# T4p0.net
KiCad netlist of a schematic drawn in EAGLE
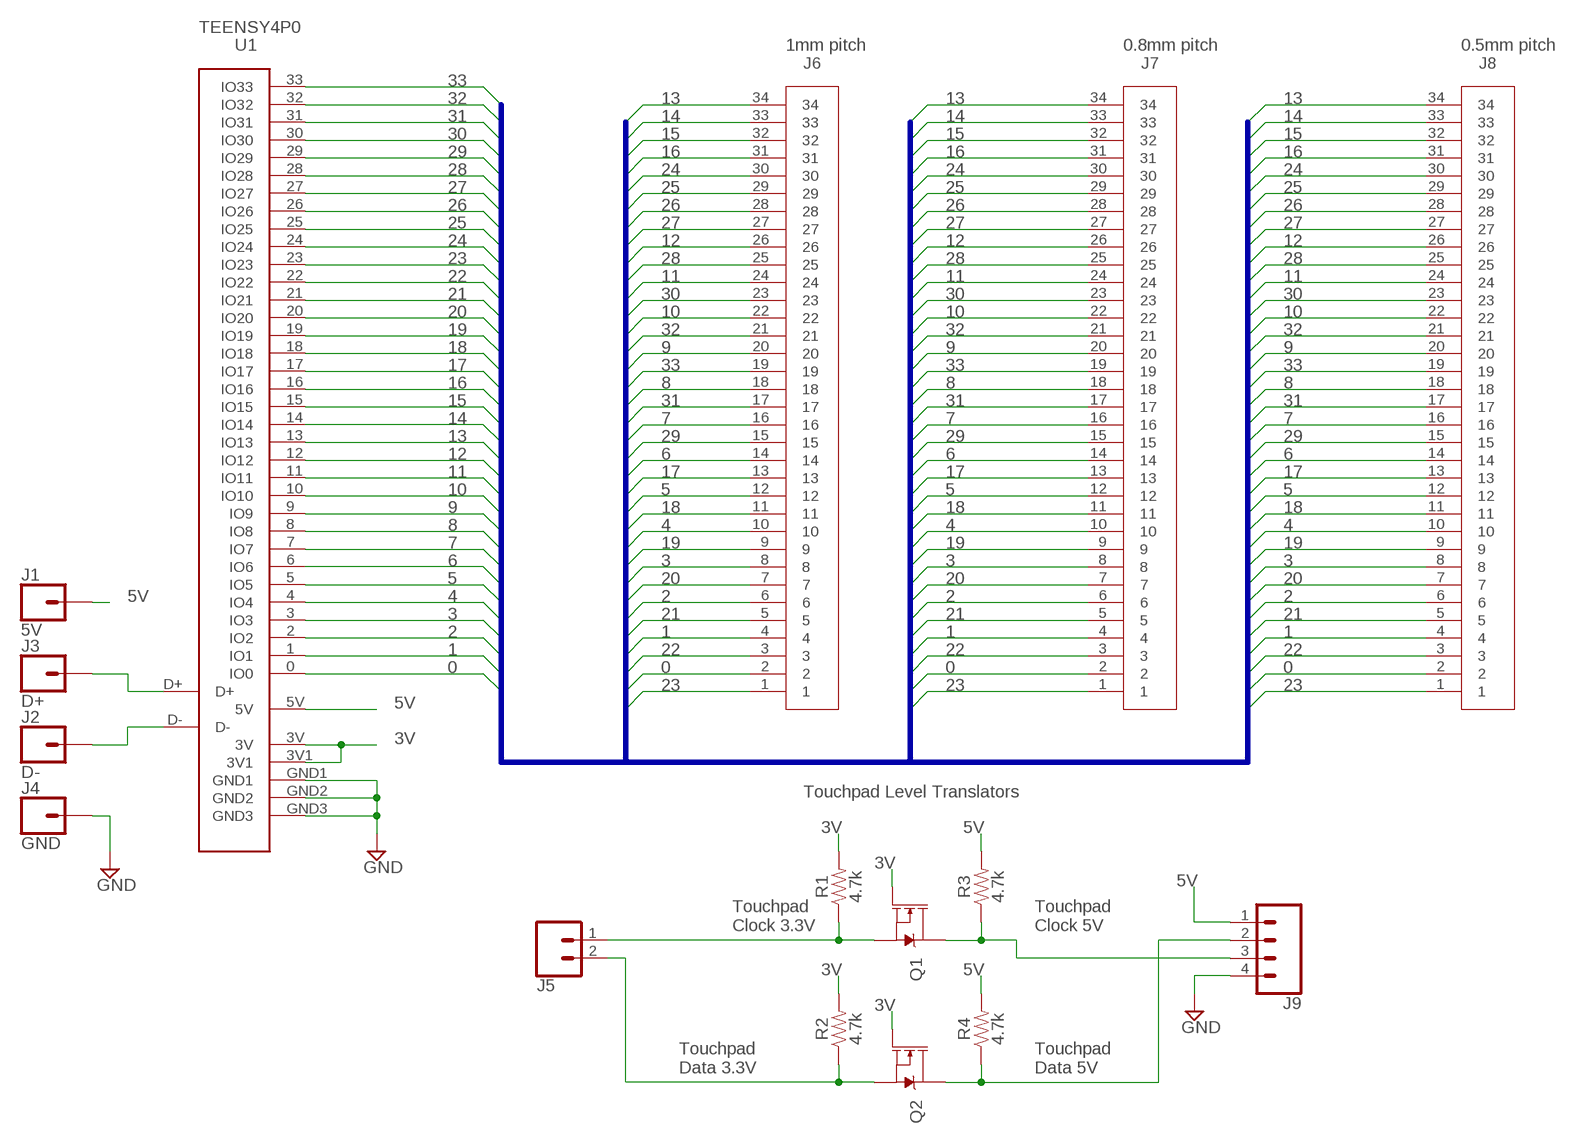
[diagram p0: schematic, sheet 1]

(export (version "E")
  (design (tool "Eeschema 10.0.6"))
  (components
    (comp (ref "J1")
      (value "5V")
      (footprint "eagle-import:1X01_NO_SILK")
      (libsource (lib "eagle-import") (part "CONN_01PTH_NO_SILK_YES_STOP"))
    )
    (comp (ref "J2")
      (value "D-")
      (footprint "eagle-import:1X01_NO_SILK")
      (libsource (lib "eagle-import") (part "CONN_01PTH_NO_SILK_YES_STOP"))
    )
    (comp (ref "J3")
      (value "D+")
      (footprint "eagle-import:1X01_NO_SILK")
      (libsource (lib "eagle-import") (part "CONN_01PTH_NO_SILK_YES_STOP"))
    )
    (comp (ref "J4")
      (value "GND")
      (footprint "eagle-import:1X01_NO_SILK")
      (libsource (lib "eagle-import") (part "CONN_01PTH_NO_SILK_YES_STOP"))
    )
    (comp (ref "J5")
      (value "CONN_021X02_NO_SILK")
      (footprint "eagle-import:1X02_NO_SILK")
      (libsource (lib "eagle-import") (part "CONN_021X02_NO_SILK"))
    )
    (comp (ref "J6")
      (value "FPC34")
      (footprint "eagle-import:FPC34")
      (libsource (lib "eagle-import") (part "FPC34"))
    )
    (comp (ref "J7")
      (value "FPC34_P8MM")
      (footprint "eagle-import:FPC34_P8MM")
      (libsource (lib "eagle-import") (part "FPC34_P8MM"))
    )
    (comp (ref "J8")
      (value "FPC34_P5MM")
      (footprint "eagle-import:FPC34_P5MM")
      (libsource (lib "eagle-import") (part "FPC34_P5MM"))
    )
    (comp (ref "J9")
      (value "CONN_041X04_NO_SILK")
      (footprint "eagle-import:1X04_NO_SILK")
      (libsource (lib "eagle-import") (part "CONN_041X04_NO_SILK"))
    )
    (comp (ref "Q1")
      (value "220mA/50V/3.5Ω")
      (footprint "eagle-import:SOT23-3")
      (libsource (lib "eagle-import") (part "MOSFET-NCH-BSS138"))
    )
    (comp (ref "Q2")
      (value "220mA/50V/3.5Ω")
      (footprint "eagle-import:SOT23-3")
      (libsource (lib "eagle-import") (part "MOSFET-NCH-BSS138"))
    )
    (comp (ref "R1")
      (value "4.7k")
      (footprint "eagle-import:0603")
      (libsource (lib "eagle-import") (part "4.7KOHM-0603-1/10W-1%"))
    )
    (comp (ref "R2")
      (value "4.7k")
      (footprint "eagle-import:0603")
      (libsource (lib "eagle-import") (part "4.7KOHM-0603-1/10W-1%"))
    )
    (comp (ref "R3")
      (value "4.7k")
      (footprint "eagle-import:0603")
      (libsource (lib "eagle-import") (part "4.7KOHM-0603-1/10W-1%"))
    )
    (comp (ref "R4")
      (value "4.7k")
      (footprint "eagle-import:0603")
      (libsource (lib "eagle-import") (part "4.7KOHM-0603-1/10W-1%"))
    )
    (comp (ref "U1")
      (value "TEENSY4P0")
      (footprint "eagle-import:TEENSY4P0")
      (libsource (lib "eagle-import") (part "TEENSY4P0"))
    )
  )
  (nets
    (net (code "1") (name "/0") (class "Default")
      (node (ref "J6") (pin "2") (pinfunction "2_2") (pintype "bidirectional"))
      (node (ref "J7") (pin "2") (pinfunction "2_2") (pintype "bidirectional"))
      (node (ref "J8") (pin "2") (pinfunction "2_2") (pintype "bidirectional"))
      (node (ref "U1") (pin "0") (pinfunction "IO0_0") (pintype "bidirectional"))
    )
    (net (code "2") (name "/1") (class "Default")
      (node (ref "J6") (pin "4") (pinfunction "4_4") (pintype "bidirectional"))
      (node (ref "J7") (pin "4") (pinfunction "4_4") (pintype "bidirectional"))
      (node (ref "J8") (pin "4") (pinfunction "4_4") (pintype "bidirectional"))
      (node (ref "U1") (pin "1") (pinfunction "IO1_1") (pintype "bidirectional"))
    )
    (net (code "3") (name "/2") (class "Default")
      (node (ref "J6") (pin "6") (pinfunction "6_6") (pintype "bidirectional"))
      (node (ref "J7") (pin "6") (pinfunction "6_6") (pintype "bidirectional"))
      (node (ref "J8") (pin "6") (pinfunction "6_6") (pintype "bidirectional"))
      (node (ref "U1") (pin "2") (pinfunction "IO2_2") (pintype "bidirectional"))
    )
    (net (code "4") (name "/3") (class "Default")
      (node (ref "J6") (pin "8") (pinfunction "8_8") (pintype "bidirectional"))
      (node (ref "J7") (pin "8") (pinfunction "8_8") (pintype "bidirectional"))
      (node (ref "J8") (pin "8") (pinfunction "8_8") (pintype "bidirectional"))
      (node (ref "U1") (pin "3") (pinfunction "IO3_3") (pintype "bidirectional"))
    )
    (net (code "5") (name "/3V") (class "Default")
      (node (ref "Q1") (pin "1") (pinfunction "G_1") (pintype "bidirectional"))
      (node (ref "Q2") (pin "1") (pinfunction "G_1") (pintype "bidirectional"))
      (node (ref "R1") (pin "2") (pinfunction "2_2") (pintype "passive"))
      (node (ref "R2") (pin "2") (pinfunction "2_2") (pintype "passive"))
      (node (ref "U1") (pin "3V") (pinfunction "3V_3V") (pintype "bidirectional"))
      (node (ref "U1") (pin "3V1") (pinfunction "3V1_3V1") (pintype "bidirectional"))
    )
    (net (code "6") (name "/4") (class "Default")
      (node (ref "J6") (pin "10") (pinfunction "10_10") (pintype "bidirectional"))
      (node (ref "J7") (pin "10") (pinfunction "10_10") (pintype "bidirectional"))
      (node (ref "J8") (pin "10") (pinfunction "10_10") (pintype "bidirectional"))
      (node (ref "U1") (pin "4") (pinfunction "IO4_4") (pintype "bidirectional"))
    )
    (net (code "7") (name "/5") (class "Default")
      (node (ref "J6") (pin "12") (pinfunction "12_12") (pintype "bidirectional"))
      (node (ref "J7") (pin "12") (pinfunction "12_12") (pintype "bidirectional"))
      (node (ref "J8") (pin "12") (pinfunction "12_12") (pintype "bidirectional"))
      (node (ref "U1") (pin "5") (pinfunction "IO5_5") (pintype "bidirectional"))
    )
    (net (code "8") (name "/5V") (class "Default")
      (node (ref "J1") (pin "1") (pinfunction "1_1") (pintype "passive"))
      (node (ref "J9") (pin "1") (pinfunction "1_1") (pintype "passive"))
      (node (ref "R3") (pin "2") (pinfunction "2_2") (pintype "passive"))
      (node (ref "R4") (pin "2") (pinfunction "2_2") (pintype "passive"))
      (node (ref "U1") (pin "5V") (pinfunction "5V_5V") (pintype "bidirectional"))
    )
    (net (code "9") (name "/6") (class "Default")
      (node (ref "J6") (pin "14") (pinfunction "14_14") (pintype "bidirectional"))
      (node (ref "J7") (pin "14") (pinfunction "14_14") (pintype "bidirectional"))
      (node (ref "J8") (pin "14") (pinfunction "14_14") (pintype "bidirectional"))
      (node (ref "U1") (pin "6") (pinfunction "IO6_6") (pintype "bidirectional"))
    )
    (net (code "10") (name "/7") (class "Default")
      (node (ref "J6") (pin "16") (pinfunction "16_16") (pintype "bidirectional"))
      (node (ref "J7") (pin "16") (pinfunction "16_16") (pintype "bidirectional"))
      (node (ref "J8") (pin "16") (pinfunction "16_16") (pintype "bidirectional"))
      (node (ref "U1") (pin "7") (pinfunction "IO7_7") (pintype "bidirectional"))
    )
    (net (code "11") (name "/8") (class "Default")
      (node (ref "J6") (pin "18") (pinfunction "18_18") (pintype "bidirectional"))
      (node (ref "J7") (pin "18") (pinfunction "18_18") (pintype "bidirectional"))
      (node (ref "J8") (pin "18") (pinfunction "18_18") (pintype "bidirectional"))
      (node (ref "U1") (pin "8") (pinfunction "IO8_8") (pintype "bidirectional"))
    )
    (net (code "12") (name "/9") (class "Default")
      (node (ref "J6") (pin "20") (pinfunction "20_20") (pintype "bidirectional"))
      (node (ref "J7") (pin "20") (pinfunction "20_20") (pintype "bidirectional"))
      (node (ref "J8") (pin "20") (pinfunction "20_20") (pintype "bidirectional"))
      (node (ref "U1") (pin "9") (pinfunction "IO9_9") (pintype "bidirectional"))
    )
    (net (code "13") (name "/10") (class "Default")
      (node (ref "J6") (pin "22") (pinfunction "22_22") (pintype "bidirectional"))
      (node (ref "J7") (pin "22") (pinfunction "22_22") (pintype "bidirectional"))
      (node (ref "J8") (pin "22") (pinfunction "22_22") (pintype "bidirectional"))
      (node (ref "U1") (pin "10") (pinfunction "IO10_10") (pintype "bidirectional"))
    )
    (net (code "14") (name "/11") (class "Default")
      (node (ref "J6") (pin "24") (pinfunction "24_24") (pintype "bidirectional"))
      (node (ref "J7") (pin "24") (pinfunction "24_24") (pintype "bidirectional"))
      (node (ref "J8") (pin "24") (pinfunction "24_24") (pintype "bidirectional"))
      (node (ref "U1") (pin "11") (pinfunction "IO11_11") (pintype "bidirectional"))
    )
    (net (code "15") (name "/12") (class "Default")
      (node (ref "J6") (pin "26") (pinfunction "26_26") (pintype "bidirectional"))
      (node (ref "J7") (pin "26") (pinfunction "26_26") (pintype "bidirectional"))
      (node (ref "J8") (pin "26") (pinfunction "26_26") (pintype "bidirectional"))
      (node (ref "U1") (pin "12") (pinfunction "IO12_12") (pintype "bidirectional"))
    )
    (net (code "16") (name "/13") (class "Default")
      (node (ref "J6") (pin "34") (pinfunction "34_34") (pintype "bidirectional"))
      (node (ref "J7") (pin "34") (pinfunction "34_34") (pintype "bidirectional"))
      (node (ref "J8") (pin "34") (pinfunction "34_34") (pintype "bidirectional"))
      (node (ref "U1") (pin "13") (pinfunction "IO13_13") (pintype "bidirectional"))
    )
    (net (code "17") (name "/14") (class "Default")
      (node (ref "J6") (pin "33") (pinfunction "33_33") (pintype "bidirectional"))
      (node (ref "J7") (pin "33") (pinfunction "33_33") (pintype "bidirectional"))
      (node (ref "J8") (pin "33") (pinfunction "33_33") (pintype "bidirectional"))
      (node (ref "U1") (pin "14") (pinfunction "IO14_14") (pintype "bidirectional"))
    )
    (net (code "18") (name "/15") (class "Default")
      (node (ref "J6") (pin "32") (pinfunction "32_32") (pintype "bidirectional"))
      (node (ref "J7") (pin "32") (pinfunction "32_32") (pintype "bidirectional"))
      (node (ref "J8") (pin "32") (pinfunction "32_32") (pintype "bidirectional"))
      (node (ref "U1") (pin "15") (pinfunction "IO15_15") (pintype "bidirectional"))
    )
    (net (code "19") (name "/16") (class "Default")
      (node (ref "J6") (pin "31") (pinfunction "31_31") (pintype "bidirectional"))
      (node (ref "J7") (pin "31") (pinfunction "31_31") (pintype "bidirectional"))
      (node (ref "J8") (pin "31") (pinfunction "31_31") (pintype "bidirectional"))
      (node (ref "U1") (pin "16") (pinfunction "IO16_16") (pintype "bidirectional"))
    )
    (net (code "20") (name "/17") (class "Default")
      (node (ref "J6") (pin "13") (pinfunction "13_13") (pintype "bidirectional"))
      (node (ref "J7") (pin "13") (pinfunction "13_13") (pintype "bidirectional"))
      (node (ref "J8") (pin "13") (pinfunction "13_13") (pintype "bidirectional"))
      (node (ref "U1") (pin "17") (pinfunction "IO17_17") (pintype "bidirectional"))
    )
    (net (code "21") (name "/18") (class "Default")
      (node (ref "J6") (pin "11") (pinfunction "11_11") (pintype "bidirectional"))
      (node (ref "J7") (pin "11") (pinfunction "11_11") (pintype "bidirectional"))
      (node (ref "J8") (pin "11") (pinfunction "11_11") (pintype "bidirectional"))
      (node (ref "U1") (pin "18") (pinfunction "IO18_18") (pintype "bidirectional"))
    )
    (net (code "22") (name "/19") (class "Default")
      (node (ref "J6") (pin "9") (pinfunction "9_9") (pintype "bidirectional"))
      (node (ref "J7") (pin "9") (pinfunction "9_9") (pintype "bidirectional"))
      (node (ref "J8") (pin "9") (pinfunction "9_9") (pintype "bidirectional"))
      (node (ref "U1") (pin "19") (pinfunction "IO19_19") (pintype "bidirectional"))
    )
    (net (code "23") (name "/20") (class "Default")
      (node (ref "J6") (pin "7") (pinfunction "7_7") (pintype "bidirectional"))
      (node (ref "J7") (pin "7") (pinfunction "7_7") (pintype "bidirectional"))
      (node (ref "J8") (pin "7") (pinfunction "7_7") (pintype "bidirectional"))
      (node (ref "U1") (pin "20") (pinfunction "IO20_20") (pintype "bidirectional"))
    )
    (net (code "24") (name "/21") (class "Default")
      (node (ref "J6") (pin "5") (pinfunction "5_5") (pintype "bidirectional"))
      (node (ref "J7") (pin "5") (pinfunction "5_5") (pintype "bidirectional"))
      (node (ref "J8") (pin "5") (pinfunction "5_5") (pintype "bidirectional"))
      (node (ref "U1") (pin "21") (pinfunction "IO21_21") (pintype "bidirectional"))
    )
    (net (code "25") (name "/22") (class "Default")
      (node (ref "J6") (pin "3") (pinfunction "3_3") (pintype "bidirectional"))
      (node (ref "J7") (pin "3") (pinfunction "3_3") (pintype "bidirectional"))
      (node (ref "J8") (pin "3") (pinfunction "3_3") (pintype "bidirectional"))
      (node (ref "U1") (pin "22") (pinfunction "IO22_22") (pintype "bidirectional"))
    )
    (net (code "26") (name "/23") (class "Default")
      (node (ref "J6") (pin "1") (pinfunction "1_1") (pintype "bidirectional"))
      (node (ref "J7") (pin "1") (pinfunction "1_1") (pintype "bidirectional"))
      (node (ref "J8") (pin "1") (pinfunction "1_1") (pintype "bidirectional"))
      (node (ref "U1") (pin "23") (pinfunction "IO23_23") (pintype "bidirectional"))
    )
    (net (code "27") (name "/24") (class "Default")
      (node (ref "J6") (pin "30") (pinfunction "30_30") (pintype "bidirectional"))
      (node (ref "J7") (pin "30") (pinfunction "30_30") (pintype "bidirectional"))
      (node (ref "J8") (pin "30") (pinfunction "30_30") (pintype "bidirectional"))
      (node (ref "U1") (pin "24") (pinfunction "IO24_24") (pintype "bidirectional"))
    )
    (net (code "28") (name "/25") (class "Default")
      (node (ref "J6") (pin "29") (pinfunction "29_29") (pintype "bidirectional"))
      (node (ref "J7") (pin "29") (pinfunction "29_29") (pintype "bidirectional"))
      (node (ref "J8") (pin "29") (pinfunction "29_29") (pintype "bidirectional"))
      (node (ref "U1") (pin "25") (pinfunction "IO25_25") (pintype "bidirectional"))
    )
    (net (code "29") (name "/26") (class "Default")
      (node (ref "J6") (pin "28") (pinfunction "28_28") (pintype "bidirectional"))
      (node (ref "J7") (pin "28") (pinfunction "28_28") (pintype "bidirectional"))
      (node (ref "J8") (pin "28") (pinfunction "28_28") (pintype "bidirectional"))
      (node (ref "U1") (pin "26") (pinfunction "IO26_26") (pintype "bidirectional"))
    )
    (net (code "30") (name "/27") (class "Default")
      (node (ref "J6") (pin "27") (pinfunction "27_27") (pintype "bidirectional"))
      (node (ref "J7") (pin "27") (pinfunction "27_27") (pintype "bidirectional"))
      (node (ref "J8") (pin "27") (pinfunction "27_27") (pintype "bidirectional"))
      (node (ref "U1") (pin "27") (pinfunction "IO27_27") (pintype "bidirectional"))
    )
    (net (code "31") (name "/28") (class "Default")
      (node (ref "J6") (pin "25") (pinfunction "25_25") (pintype "bidirectional"))
      (node (ref "J7") (pin "25") (pinfunction "25_25") (pintype "bidirectional"))
      (node (ref "J8") (pin "25") (pinfunction "25_25") (pintype "bidirectional"))
      (node (ref "U1") (pin "28") (pinfunction "IO28_28") (pintype "bidirectional"))
    )
    (net (code "32") (name "/29") (class "Default")
      (node (ref "J6") (pin "15") (pinfunction "15_15") (pintype "bidirectional"))
      (node (ref "J7") (pin "15") (pinfunction "15_15") (pintype "bidirectional"))
      (node (ref "J8") (pin "15") (pinfunction "15_15") (pintype "bidirectional"))
      (node (ref "U1") (pin "29") (pinfunction "IO29_29") (pintype "bidirectional"))
    )
    (net (code "33") (name "/30") (class "Default")
      (node (ref "J6") (pin "23") (pinfunction "23_23") (pintype "bidirectional"))
      (node (ref "J7") (pin "23") (pinfunction "23_23") (pintype "bidirectional"))
      (node (ref "J8") (pin "23") (pinfunction "23_23") (pintype "bidirectional"))
      (node (ref "U1") (pin "30") (pinfunction "IO30_30") (pintype "bidirectional"))
    )
    (net (code "34") (name "/31") (class "Default")
      (node (ref "J6") (pin "17") (pinfunction "17_17") (pintype "bidirectional"))
      (node (ref "J7") (pin "17") (pinfunction "17_17") (pintype "bidirectional"))
      (node (ref "J8") (pin "17") (pinfunction "17_17") (pintype "bidirectional"))
      (node (ref "U1") (pin "31") (pinfunction "IO31_31") (pintype "bidirectional"))
    )
    (net (code "35") (name "/32") (class "Default")
      (node (ref "J6") (pin "21") (pinfunction "21_21") (pintype "bidirectional"))
      (node (ref "J7") (pin "21") (pinfunction "21_21") (pintype "bidirectional"))
      (node (ref "J8") (pin "21") (pinfunction "21_21") (pintype "bidirectional"))
      (node (ref "U1") (pin "32") (pinfunction "IO32_32") (pintype "bidirectional"))
    )
    (net (code "36") (name "/33") (class "Default")
      (node (ref "J6") (pin "19") (pinfunction "19_19") (pintype "bidirectional"))
      (node (ref "J7") (pin "19") (pinfunction "19_19") (pintype "bidirectional"))
      (node (ref "J8") (pin "19") (pinfunction "19_19") (pintype "bidirectional"))
      (node (ref "U1") (pin "33") (pinfunction "IO33_33") (pintype "bidirectional"))
    )
    (net (code "37") (name "GND") (class "Default")
      (node (ref "J4") (pin "1") (pinfunction "1_1") (pintype "passive"))
      (node (ref "J9") (pin "4") (pinfunction "4_4") (pintype "passive"))
      (node (ref "U1") (pin "GND1") (pinfunction "GND1_GND1") (pintype "bidirectional"))
      (node (ref "U1") (pin "GND2") (pinfunction "GND2_GND2") (pintype "bidirectional"))
      (node (ref "U1") (pin "GND3") (pinfunction "GND3_GND3") (pintype "bidirectional"))
    )
    (net (code "38") (name "Net-(J2-Pad1)") (class "Default")
      (node (ref "J2") (pin "1") (pinfunction "1_1") (pintype "passive"))
      (node (ref "U1") (pin "D-") (pinfunction "D-_D-") (pintype "bidirectional"))
    )
    (net (code "39") (name "Net-(J3-Pad1)") (class "Default")
      (node (ref "J3") (pin "1") (pinfunction "1_1") (pintype "passive"))
      (node (ref "U1") (pin "D+") (pinfunction "D+_D+") (pintype "bidirectional"))
    )
    (net (code "40") (name "Net-(Q1-D)") (class "Default")
      (node (ref "J9") (pin "3") (pinfunction "3_3") (pintype "passive"))
      (node (ref "Q1") (pin "3") (pinfunction "D_3") (pintype "bidirectional"))
      (node (ref "R3") (pin "1") (pinfunction "1_1") (pintype "passive"))
    )
    (net (code "41") (name "Net-(Q1-S)") (class "Default")
      (node (ref "J5") (pin "1") (pinfunction "1_1") (pintype "passive"))
      (node (ref "Q1") (pin "2") (pinfunction "S_2") (pintype "bidirectional"))
      (node (ref "R1") (pin "1") (pinfunction "1_1") (pintype "passive"))
    )
    (net (code "42") (name "Net-(Q2-D)") (class "Default")
      (node (ref "J9") (pin "2") (pinfunction "2_2") (pintype "passive"))
      (node (ref "Q2") (pin "3") (pinfunction "D_3") (pintype "bidirectional"))
      (node (ref "R4") (pin "1") (pinfunction "1_1") (pintype "passive"))
    )
    (net (code "43") (name "Net-(Q2-S)") (class "Default")
      (node (ref "J5") (pin "2") (pinfunction "2_2") (pintype "passive"))
      (node (ref "Q2") (pin "2") (pinfunction "S_2") (pintype "bidirectional"))
      (node (ref "R2") (pin "1") (pinfunction "1_1") (pintype "passive"))
    )
  )
)
